# osi-power_dc_rev_0.net
KiCad netlist of a schematic drawn in EAGLE
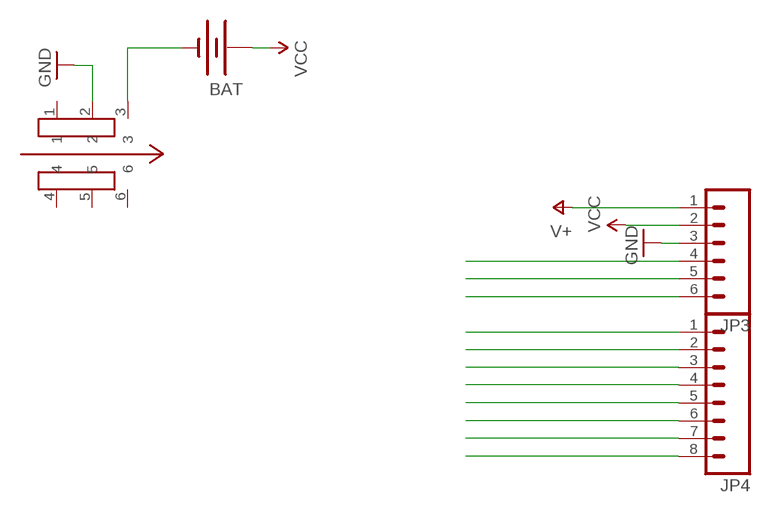
[diagram p0: schematic, sheet 1]

(export (version "E")
  (design (tool "Eeschema 10.0.6"))
  (components
    (comp (ref "BAT")
      (value "BATTERY20PTH")
      (footprint "eagle-import:BATTCOM_20MM_PTH")
      (libsource (lib "eagle-import") (part "BATTERY20PTH"))
    )
    (comp (ref "JP3")
      (value "M06SIP")
      (footprint "eagle-import:1X06")
      (libsource (lib "eagle-import") (part "M06SIP"))
    )
    (comp (ref "JP4")
      (value "M081X08")
      (footprint "eagle-import:1X08")
      (libsource (lib "eagle-import") (part "M081X08"))
    )
    (comp (ref "U$1")
      (value "SWITCH")
      (footprint "eagle-import:SWITCH")
      (libsource (lib "eagle-import") (part "SWITCH"))
    )
  )
  (nets
    (net (code "1") (name "GND") (class "Default")
      (node (ref "JP3") (pin "3") (pinfunction "3_3") (pintype "passive"))
      (node (ref "U$1") (pin "2") (pinfunction "2_2") (pintype "bidirectional"))
    )
    (net (code "2") (name "Net-(BAT--)") (class "Default")
      (node (ref "BAT") (pin "2") (pinfunction "-_2") (pintype "power_in"))
      (node (ref "U$1") (pin "3") (pinfunction "3_3") (pintype "bidirectional"))
    )
    (net (code "3") (name "V+") (class "Default")
      (node (ref "JP3") (pin "1") (pinfunction "1_1") (pintype "passive"))
    )
    (net (code "4") (name "VCC") (class "Default")
      (node (ref "BAT") (pin "1") (pinfunction "+_1") (pintype "power_in"))
      (node (ref "JP3") (pin "2") (pinfunction "2_2") (pintype "passive"))
    )
    (net (code "5") (name "unconnected-(JP3-Pad4)") (class "Default")
      (node (ref "JP3") (pin "4") (pinfunction "4_4") (pintype "passive"))
    )
    (net (code "6") (name "unconnected-(JP3-Pad5)") (class "Default")
      (node (ref "JP3") (pin "5") (pinfunction "5_5") (pintype "passive"))
    )
    (net (code "7") (name "unconnected-(JP3-Pad6)") (class "Default")
      (node (ref "JP3") (pin "6") (pinfunction "6_6") (pintype "passive"))
    )
    (net (code "8") (name "unconnected-(JP4-Pad1)") (class "Default")
      (node (ref "JP4") (pin "1") (pinfunction "1_1") (pintype "passive"))
    )
    (net (code "9") (name "unconnected-(JP4-Pad2)") (class "Default")
      (node (ref "JP4") (pin "2") (pinfunction "2_2") (pintype "passive"))
    )
    (net (code "10") (name "unconnected-(JP4-Pad3)") (class "Default")
      (node (ref "JP4") (pin "3") (pinfunction "3_3") (pintype "passive"))
    )
    (net (code "11") (name "unconnected-(JP4-Pad4)") (class "Default")
      (node (ref "JP4") (pin "4") (pinfunction "4_4") (pintype "passive"))
    )
    (net (code "12") (name "unconnected-(JP4-Pad5)") (class "Default")
      (node (ref "JP4") (pin "5") (pinfunction "5_5") (pintype "passive"))
    )
    (net (code "13") (name "unconnected-(JP4-Pad6)") (class "Default")
      (node (ref "JP4") (pin "6") (pinfunction "6_6") (pintype "passive"))
    )
    (net (code "14") (name "unconnected-(JP4-Pad7)") (class "Default")
      (node (ref "JP4") (pin "7") (pinfunction "7_7") (pintype "passive"))
    )
    (net (code "15") (name "unconnected-(JP4-Pad8)") (class "Default")
      (node (ref "JP4") (pin "8") (pinfunction "8_8") (pintype "passive"))
    )
    (net (code "16") (name "unconnected-(U$1-Pad1)") (class "Default")
      (node (ref "U$1") (pin "1") (pinfunction "1_1") (pintype "bidirectional"))
    )
    (net (code "17") (name "unconnected-(U$1-Pad4)") (class "Default")
      (node (ref "U$1") (pin "4") (pinfunction "4_4") (pintype "bidirectional"))
    )
    (net (code "18") (name "unconnected-(U$1-Pad5)") (class "Default")
      (node (ref "U$1") (pin "5") (pinfunction "5_5") (pintype "bidirectional"))
    )
    (net (code "19") (name "unconnected-(U$1-Pad6)") (class "Default")
      (node (ref "U$1") (pin "6") (pinfunction "6_6") (pintype "bidirectional"))
    )
  )
)
